# blinkm_mk2v5bb.net
KiCad netlist of a schematic drawn in EAGLE
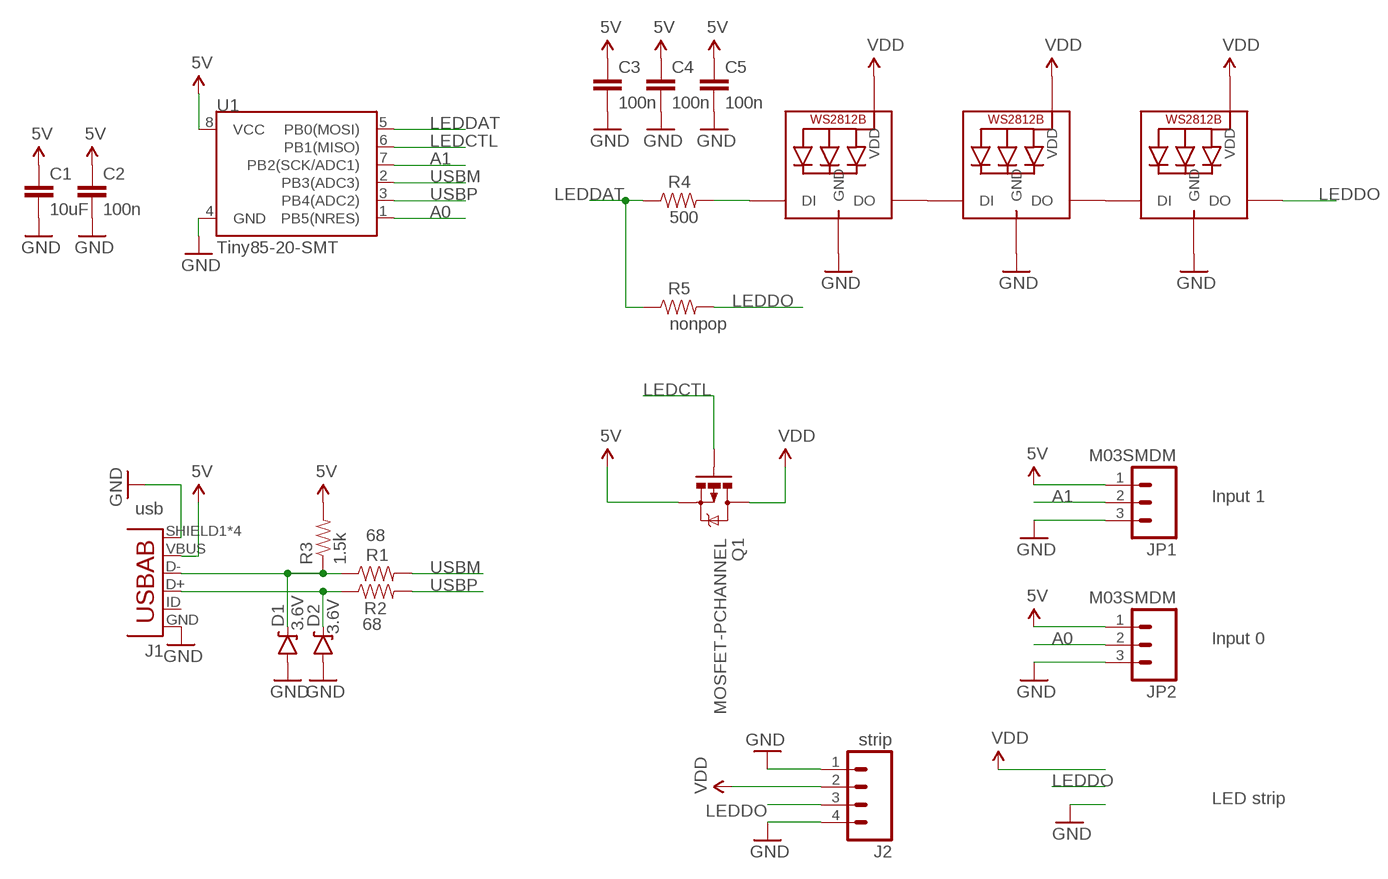
[diagram p0: schematic, sheet 1]

(export (version "E")
  (design (tool "Eeschema 10.0.6"))
  (components
    (comp (ref "C1")
      (value "10uF")
      (footprint "eagle-import:0603-CAP")
      (libsource (lib "eagle-import") (part "CAP0603-CAP"))
    )
    (comp (ref "C2")
      (value "100n")
      (footprint "eagle-import:0603-CAP")
      (libsource (lib "eagle-import") (part "CAP0603-CAP"))
    )
    (comp (ref "C3")
      (value "100n")
      (footprint "eagle-import:0603-CAP")
      (libsource (lib "eagle-import") (part "CAP0603-CAP"))
    )
    (comp (ref "C4")
      (value "100n")
      (footprint "eagle-import:0603-CAP")
      (libsource (lib "eagle-import") (part "CAP0603-CAP"))
    )
    (comp (ref "C5")
      (value "100n")
      (footprint "eagle-import:0603-CAP")
      (libsource (lib "eagle-import") (part "CAP0603-CAP"))
    )
    (comp (ref "D1")
      (value "3.6V")
      (footprint "eagle-import:SOD-323")
      (libsource (lib "eagle-import") (part "DIODE-ZENER3.3V"))
    )
    (comp (ref "D2")
      (value "3.6V")
      (footprint "eagle-import:SOD-323")
      (libsource (lib "eagle-import") (part "DIODE-ZENER3.3V"))
    )
    (comp (ref "J1")
      (value "usb")
      (footprint "eagle-import:USB-AB-MICRO-SMD")
      (libsource (lib "eagle-import") (part "USB-AB"))
    )
    (comp (ref "J2")
      (value "strip")
      (footprint "eagle-import:1X04_NO_SILK_ALL_ROUND")
      (libsource (lib "eagle-import") (part "M04NO_SILK_ALL_ROUND"))
    )
    (comp (ref "JP1")
      (value "M03SMDM")
      (footprint "eagle-import:1X03-SMD-MINIMAL")
      (libsource (lib "eagle-import") (part "M03SMDM"))
    )
    (comp (ref "JP2")
      (value "M03SMDM")
      (footprint "eagle-import:1X03-SMD-MINIMAL")
      (libsource (lib "eagle-import") (part "M03SMDM"))
    )
    (comp (ref "LED1")
      (value "WS2812B3535")
      (footprint "eagle-import:LED3535")
      (libsource (lib "eagle-import") (part "WS2812B3535"))
    )
    (comp (ref "LED2")
      (value "WS2812B3535")
      (footprint "eagle-import:LED3535")
      (libsource (lib "eagle-import") (part "WS2812B3535"))
    )
    (comp (ref "LED3")
      (value "WS2812B3535")
      (footprint "eagle-import:LED3535")
      (libsource (lib "eagle-import") (part "WS2812B3535"))
    )
    (comp (ref "Q1")
      (value "MOSFET-PCHANNEL")
      (footprint "eagle-import:SOT23-3")
      (libsource (lib "eagle-import") (part "MOSFET-PCHANNEL"))
    )
    (comp (ref "R1")
      (value "68")
      (footprint "eagle-import:0603-RES")
      (libsource (lib "eagle-import") (part "RESISTOR0603-RES"))
    )
    (comp (ref "R2")
      (value "68")
      (footprint "eagle-import:0603-RES")
      (libsource (lib "eagle-import") (part "RESISTOR0603-RES"))
    )
    (comp (ref "R3")
      (value "1.5k")
      (footprint "eagle-import:0603-RES")
      (libsource (lib "eagle-import") (part "RESISTOR0603-RES"))
    )
    (comp (ref "R4")
      (value "500")
      (footprint "eagle-import:0603-RES")
      (libsource (lib "eagle-import") (part "RESISTOR0603-RES"))
    )
    (comp (ref "R5")
      (value "nonpop")
      (footprint "eagle-import:0603-RES")
      (libsource (lib "eagle-import") (part "RESISTOR0603-RES"))
    )
    (comp (ref "U1")
      (value "Tiny85-20-SMT")
      (footprint "eagle-import:SO08-EIAJ")
      (libsource (lib "eagle-import") (part "ATTINY45TINY85-20-SMT"))
    )
  )
  (nets
    (net (code "1") (name "/A0") (class "Default")
      (node (ref "JP2") (pin "2") (pinfunction "2_2") (pintype "passive"))
      (node (ref "U1") (pin "1") (pinfunction "PB5(NRES)_1") (pintype "bidirectional"))
    )
    (net (code "2") (name "/A1") (class "Default")
      (node (ref "JP1") (pin "2") (pinfunction "2_2") (pintype "passive"))
      (node (ref "U1") (pin "7") (pinfunction "PB2(SCK/ADC1)_7") (pintype "bidirectional"))
    )
    (net (code "3") (name "/LEDCTL") (class "Default")
      (node (ref "Q1") (pin "1") (pinfunction "G_1") (pintype "passive"))
      (node (ref "U1") (pin "6") (pinfunction "PB1(MISO)_6") (pintype "bidirectional"))
    )
    (net (code "4") (name "/LEDDAT") (class "Default")
      (node (ref "R4") (pin "1") (pinfunction "1_1") (pintype "passive"))
      (node (ref "R5") (pin "1") (pinfunction "1_1") (pintype "passive"))
      (node (ref "U1") (pin "5") (pinfunction "PB0(MOSI)_5") (pintype "bidirectional"))
    )
    (net (code "5") (name "/LEDDO") (class "Default")
      (node (ref "J2") (pin "3") (pinfunction "3_3") (pintype "passive"))
      (node (ref "LED3") (pin "3") (pinfunction "DO_3") (pintype "output"))
      (node (ref "R5") (pin "2") (pinfunction "2_2") (pintype "passive"))
    )
    (net (code "6") (name "/USBM") (class "Default")
      (node (ref "R1") (pin "2") (pinfunction "2_2") (pintype "passive"))
      (node (ref "U1") (pin "2") (pinfunction "PB3(ADC3)_2") (pintype "bidirectional"))
    )
    (net (code "7") (name "/USBP") (class "Default")
      (node (ref "R2") (pin "2") (pinfunction "2_2") (pintype "passive"))
      (node (ref "U1") (pin "3") (pinfunction "PB4(ADC2)_3") (pintype "bidirectional"))
    )
    (net (code "8") (name "5V") (class "Default")
      (node (ref "C1") (pin "1") (pinfunction "1_1") (pintype "passive"))
      (node (ref "C2") (pin "1") (pinfunction "1_1") (pintype "passive"))
      (node (ref "C3") (pin "1") (pinfunction "1_1") (pintype "passive"))
      (node (ref "C4") (pin "1") (pinfunction "1_1") (pintype "passive"))
      (node (ref "C5") (pin "1") (pinfunction "1_1") (pintype "passive"))
      (node (ref "J1") (pin "VBUS") (pinfunction "VBUS_VBUS") (pintype "bidirectional"))
      (node (ref "JP1") (pin "1") (pinfunction "1_1") (pintype "passive"))
      (node (ref "JP2") (pin "1") (pinfunction "1_1") (pintype "passive"))
      (node (ref "Q1") (pin "2") (pinfunction "S_2") (pintype "passive"))
      (node (ref "R3") (pin "2") (pinfunction "2_2") (pintype "passive"))
      (node (ref "U1") (pin "8") (pinfunction "VCC_8") (pintype "bidirectional"))
    )
    (net (code "9") (name "GND") (class "Default")
      (node (ref "C1") (pin "2") (pinfunction "2_2") (pintype "passive"))
      (node (ref "C2") (pin "2") (pinfunction "2_2") (pintype "passive"))
      (node (ref "C3") (pin "2") (pinfunction "2_2") (pintype "passive"))
      (node (ref "C4") (pin "2") (pinfunction "2_2") (pintype "passive"))
      (node (ref "C5") (pin "2") (pinfunction "2_2") (pintype "passive"))
      (node (ref "D1") (pin "A") (pinfunction "A_A") (pintype "passive"))
      (node (ref "D2") (pin "A") (pinfunction "A_A") (pintype "passive"))
      (node (ref "J1") (pin "GND") (pinfunction "GND_GND") (pintype "bidirectional"))
      (node (ref "J1") (pin "SHIELD1") (pinfunction "SHIELD_SHIELD1") (pintype "bidirectional"))
      (node (ref "J1") (pin "SHIELD2") (pinfunction "SHIELD_SHIELD2") (pintype "bidirectional"))
      (node (ref "J1") (pin "SHIELD3") (pinfunction "SHIELD_SHIELD3") (pintype "bidirectional"))
      (node (ref "J1") (pin "SHIELD4") (pinfunction "SHIELD_SHIELD4") (pintype "bidirectional"))
      (node (ref "J2") (pin "1") (pinfunction "1_1") (pintype "passive"))
      (node (ref "J2") (pin "4") (pinfunction "4_4") (pintype "passive"))
      (node (ref "JP1") (pin "3") (pinfunction "3_3") (pintype "passive"))
      (node (ref "JP2") (pin "3") (pinfunction "3_3") (pintype "passive"))
      (node (ref "LED1") (pin "4") (pinfunction "GND_4") (pintype "power_in"))
      (node (ref "LED2") (pin "4") (pinfunction "GND_4") (pintype "power_in"))
      (node (ref "LED3") (pin "4") (pinfunction "GND_4") (pintype "power_in"))
      (node (ref "U1") (pin "4") (pinfunction "GND_4") (pintype "bidirectional"))
    )
    (net (code "10") (name "Net-(D1-PadC)") (class "Default")
      (node (ref "D1") (pin "C") (pinfunction "C_C") (pintype "passive"))
      (node (ref "J1") (pin "D-") (pinfunction "D-_D-") (pintype "bidirectional"))
      (node (ref "R1") (pin "1") (pinfunction "1_1") (pintype "passive"))
      (node (ref "R3") (pin "1") (pinfunction "1_1") (pintype "passive"))
    )
    (net (code "11") (name "Net-(D2-PadC)") (class "Default")
      (node (ref "D2") (pin "C") (pinfunction "C_C") (pintype "passive"))
      (node (ref "J1") (pin "D+") (pinfunction "D+_D+") (pintype "bidirectional"))
      (node (ref "R2") (pin "1") (pinfunction "1_1") (pintype "passive"))
    )
    (net (code "12") (name "Net-(LED1-DI)") (class "Default")
      (node (ref "LED1") (pin "1") (pinfunction "DI_1") (pintype "input"))
      (node (ref "R4") (pin "2") (pinfunction "2_2") (pintype "passive"))
    )
    (net (code "13") (name "Net-(LED1-DO)") (class "Default")
      (node (ref "LED1") (pin "3") (pinfunction "DO_3") (pintype "output"))
      (node (ref "LED2") (pin "1") (pinfunction "DI_1") (pintype "input"))
    )
    (net (code "14") (name "Net-(LED2-DO)") (class "Default")
      (node (ref "LED2") (pin "3") (pinfunction "DO_3") (pintype "output"))
      (node (ref "LED3") (pin "1") (pinfunction "DI_1") (pintype "input"))
    )
    (net (code "15") (name "VDD") (class "Default")
      (node (ref "J2") (pin "2") (pinfunction "2_2") (pintype "passive"))
      (node (ref "LED1") (pin "2") (pinfunction "VDD_2") (pintype "power_in"))
      (node (ref "LED2") (pin "2") (pinfunction "VDD_2") (pintype "power_in"))
      (node (ref "LED3") (pin "2") (pinfunction "VDD_2") (pintype "power_in"))
      (node (ref "Q1") (pin "3") (pinfunction "D_3") (pintype "passive"))
    )
    (net (code "16") (name "unconnected-(J1-USBID-PadID)") (class "Default")
      (node (ref "J1") (pin "ID") (pinfunction "USBID_ID") (pintype "bidirectional"))
    )
  )
)
